# bbf-pots.net
KiCad netlist of a schematic drawn in EAGLE
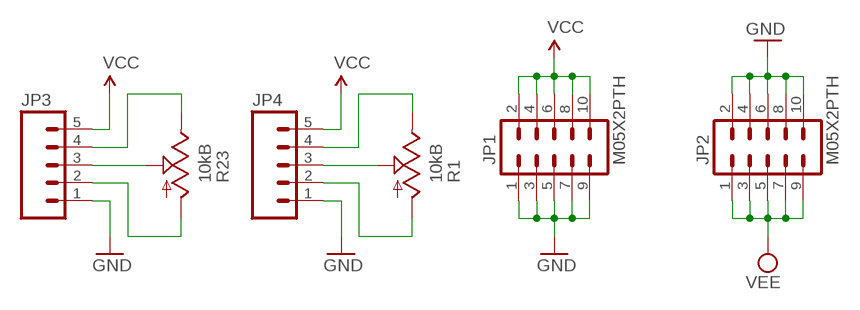
[diagram p0: schematic, sheet 1]

(export (version "E")
  (design (tool "Eeschema 10.0.6"))
  (components
    (comp (ref "JP1")
      (value "M05X2PTH")
      (footprint "eagle-import:AVR_ICSP")
      (libsource (lib "eagle-import") (part "M05X2PTH"))
    )
    (comp (ref "JP2")
      (value "M05X2PTH")
      (footprint "eagle-import:AVR_ICSP")
      (libsource (lib "eagle-import") (part "M05X2PTH"))
    )
    (comp (ref "JP3")
      (value "M05PTH")
      (footprint "eagle-import:1X05")
      (libsource (lib "eagle-import") (part "M05PTH"))
    )
    (comp (ref "JP4")
      (value "M05PTH")
      (footprint "eagle-import:1X05")
      (libsource (lib "eagle-import") (part "M05PTH"))
    )
    (comp (ref "R1")
      (value "10kB")
      (footprint "eagle-import:ALPS_POT_VERTICAL")
      (libsource (lib "eagle-import") (part "POT_USVERTICAL"))
    )
    (comp (ref "R23")
      (value "10kB")
      (footprint "eagle-import:ALPS_POT_VERTICAL")
      (libsource (lib "eagle-import") (part "POT_USVERTICAL"))
    )
  )
  (nets
    (net (code "1") (name "GND") (class "Default")
      (node (ref "JP1") (pin "1") (pinfunction "1_1") (pintype "passive"))
      (node (ref "JP1") (pin "3") (pinfunction "3_3") (pintype "passive"))
      (node (ref "JP1") (pin "5") (pinfunction "5_5") (pintype "passive"))
      (node (ref "JP1") (pin "7") (pinfunction "7_7") (pintype "passive"))
      (node (ref "JP1") (pin "9") (pinfunction "9_9") (pintype "passive"))
      (node (ref "JP2") (pin "10") (pinfunction "10_10") (pintype "passive"))
      (node (ref "JP2") (pin "2") (pinfunction "2_2") (pintype "passive"))
      (node (ref "JP2") (pin "4") (pinfunction "4_4") (pintype "passive"))
      (node (ref "JP2") (pin "6") (pinfunction "6_6") (pintype "passive"))
      (node (ref "JP2") (pin "8") (pinfunction "8_8") (pintype "passive"))
      (node (ref "JP3") (pin "1") (pinfunction "1_1") (pintype "passive"))
      (node (ref "JP4") (pin "1") (pinfunction "1_1") (pintype "passive"))
    )
    (net (code "2") (name "Net-(R1-A)") (class "Default")
      (node (ref "JP4") (pin "2") (pinfunction "2_2") (pintype "passive"))
      (node (ref "R1") (pin "P$3") (pinfunction "A_P$3") (pintype "passive"))
    )
    (net (code "3") (name "Net-(R1-E)") (class "Default")
      (node (ref "JP4") (pin "4") (pinfunction "4_4") (pintype "passive"))
      (node (ref "R1") (pin "P$1") (pinfunction "E_P$1") (pintype "passive"))
    )
    (net (code "4") (name "Net-(R1-S)") (class "Default")
      (node (ref "JP4") (pin "3") (pinfunction "3_3") (pintype "passive"))
      (node (ref "R1") (pin "P$2") (pinfunction "S_P$2") (pintype "passive"))
    )
    (net (code "5") (name "Net-(R23-A)") (class "Default")
      (node (ref "JP3") (pin "2") (pinfunction "2_2") (pintype "passive"))
      (node (ref "R23") (pin "P$3") (pinfunction "A_P$3") (pintype "passive"))
    )
    (net (code "6") (name "Net-(R23-E)") (class "Default")
      (node (ref "JP3") (pin "4") (pinfunction "4_4") (pintype "passive"))
      (node (ref "R23") (pin "P$1") (pinfunction "E_P$1") (pintype "passive"))
    )
    (net (code "7") (name "Net-(R23-S)") (class "Default")
      (node (ref "JP3") (pin "3") (pinfunction "3_3") (pintype "passive"))
      (node (ref "R23") (pin "P$2") (pinfunction "S_P$2") (pintype "passive"))
    )
    (net (code "8") (name "VCC") (class "Default")
      (node (ref "JP1") (pin "10") (pinfunction "10_10") (pintype "passive"))
      (node (ref "JP1") (pin "2") (pinfunction "2_2") (pintype "passive"))
      (node (ref "JP1") (pin "4") (pinfunction "4_4") (pintype "passive"))
      (node (ref "JP1") (pin "6") (pinfunction "6_6") (pintype "passive"))
      (node (ref "JP1") (pin "8") (pinfunction "8_8") (pintype "passive"))
      (node (ref "JP3") (pin "5") (pinfunction "5_5") (pintype "passive"))
      (node (ref "JP4") (pin "5") (pinfunction "5_5") (pintype "passive"))
    )
    (net (code "9") (name "VEE") (class "Default")
      (node (ref "JP2") (pin "1") (pinfunction "1_1") (pintype "passive"))
      (node (ref "JP2") (pin "3") (pinfunction "3_3") (pintype "passive"))
      (node (ref "JP2") (pin "5") (pinfunction "5_5") (pintype "passive"))
      (node (ref "JP2") (pin "7") (pinfunction "7_7") (pintype "passive"))
      (node (ref "JP2") (pin "9") (pinfunction "9_9") (pintype "passive"))
    )
  )
)
